# wifi_bluetooth.net
KiCad netlist of a schematic drawn in Altium Designer
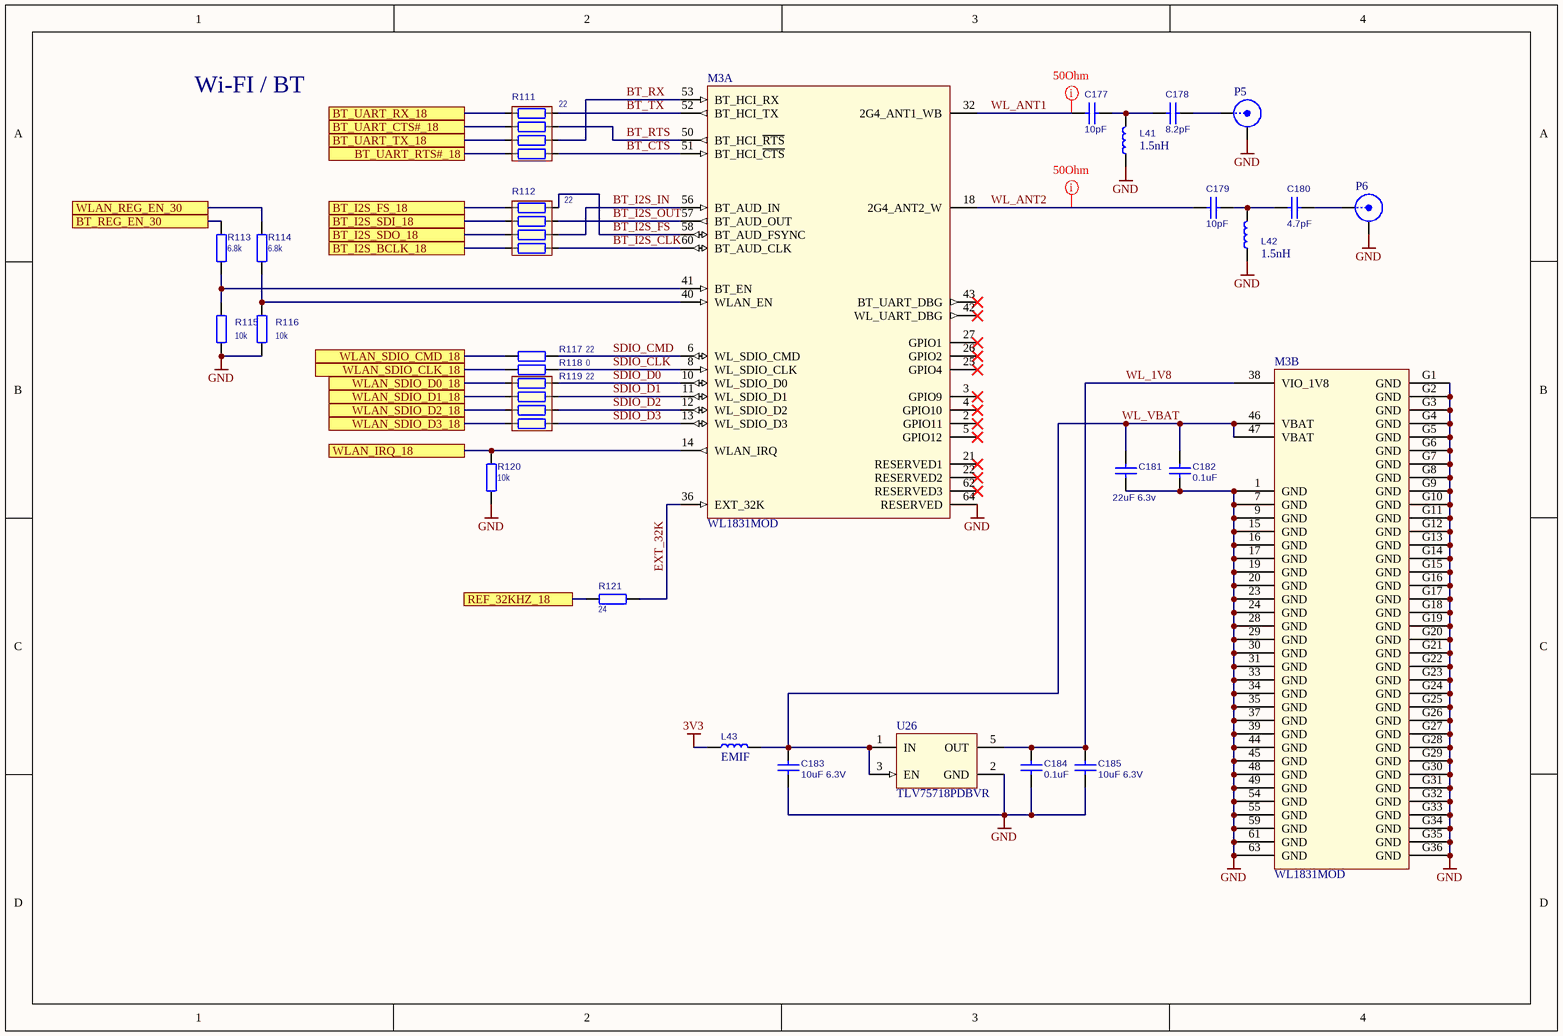
[diagram p0: wifi_bluetooth.SchDoc]

(export (version "E")
  (design (tool "Eeschema 10.0.6"))
  (components
    (comp (ref "C177")
      (value "10pF")
      (footprint "C0603")
      (description "CAP_NPOL")
      (fields (field (name "Comment") "CL10C100JB8NNNC"))
      (libsource (lib "capacitors") (part "CAP_NPOL"))
    )
    (comp (ref "C178")
      (value "8.2pF")
      (footprint "C0603")
      (description "CAP_NPOL")
      (fields (field (name "Comment") "CL10C8R2CB8NNNC"))
      (libsource (lib "capacitors") (part "CAP_NPOL"))
    )
    (comp (ref "C179")
      (value "10pF")
      (footprint "C0603")
      (description "CAP_NPOL")
      (fields (field (name "Comment") "CL10C100JB8NNNC"))
      (libsource (lib "capacitors") (part "CAP_NPOL"))
    )
    (comp (ref "C180")
      (value "4.7pF")
      (footprint "C0603")
      (description "CAP_NPOL")
      (fields (field (name "Comment") "CC0603CRNPO9BN4R7"))
      (libsource (lib "capacitors") (part "CAP_NPOL"))
    )
    (comp (ref "C181")
      (value "22uF 6.3v")
      (footprint "Capacitors:C0805")
      (description "CAP_NPOL")
      (fields (field (name "Comment") "CL21A226MQQNNNE"))
      (libsource (lib "capacitors") (part "CAP_NPOL"))
    )
    (comp (ref "C182")
      (value "0.1uF")
      (footprint "Capacitors:C0603")
      (description "CAP_NPOL")
      (fields (field (name "Comment") "C1608X7R1H104K080AA"))
      (libsource (lib "capacitors") (part "CAP_NPOL"))
    )
    (comp (ref "C183")
      (value "10uF 6.3V")
      (footprint "Capacitors:C0603")
      (description "CAP_NPOL")
      (fields (field (name "Comment") "CC0603MRX5R5BB106"))
      (libsource (lib "capacitors") (part "CAP_NPOL"))
    )
    (comp (ref "C184")
      (value "0.1uF")
      (footprint "Capacitors:C0603")
      (description "CAP_NPOL")
      (fields (field (name "Comment") "C1608X7R1H104K080AA"))
      (libsource (lib "capacitors") (part "CAP_NPOL"))
    )
    (comp (ref "C185")
      (value "10uF 6.3V")
      (footprint "Capacitors:C0603")
      (description "CAP_NPOL")
      (fields (field (name "Comment") "CC0603MRX5R5BB106"))
      (libsource (lib "capacitors") (part "CAP_NPOL"))
    )
    (comp (ref "L41")
      (value "1.5nH")
      (footprint "IND0603")
      (description "IND_WO_IRON")
      (fields (field (name "Comment") "CLH1608T-1N5S-N"))
      (libsource (lib "inductors") (part "IND_WO_IRON"))
    )
    (comp (ref "L42")
      (value "1.5nH")
      (footprint "IND0603")
      (description "IND_WO_IRON")
      (fields (field (name "Comment") "CLH1608T-1N5S-N"))
      (libsource (lib "inductors") (part "IND_WO_IRON"))
    )
    (comp (ref "L43")
      (value "EMIF")
      (footprint "IND0805")
      (description "IND_WO_IRON")
      (fields (field (name "Comment") "BLM21PG221SN1D"))
      (libsource (lib "") (part "IND_WO_IRON_1"))
    )
    (comp (ref "M3")
      (value "WL1831MOD")
      (footprint "E-13.4X13.3-N100_0.75-TOP")
      (libsource (lib "WL18xxMOD") (part "WL18xxMOD"))
    )
    (comp (ref "P5")
      (value "I-PEX")
      (footprint "RF:I-PEX")
      (fields (field (name "PUBLISHER") "Altium Limited"))
      (libsource (lib "Miscellaneous Connectors") (part "BNC"))
    )
    (comp (ref "P6")
      (value "I-PEX")
      (footprint "RF:I-PEX")
      (fields (field (name "PUBLISHER") "Altium Limited"))
      (libsource (lib "Miscellaneous Connectors") (part "BNC"))
    )
    (comp (ref "R111")
      (value "22")
      (footprint "Resistors:R0804X4")
      (description "ARRAY")
      (fields (field (name "Comment") "TC124-JR-0722RL"))
      (libsource (lib "") (part "ARRAY_1"))
    )
    (comp (ref "R112")
      (value "22")
      (footprint "Resistors:R0804X4")
      (description "ARRAY")
      (fields (field (name "Comment") "TC124-JR-0722RL"))
      (libsource (lib "") (part "ARRAY_1"))
    )
    (comp (ref "R113")
      (value "6.8k")
      (footprint "R0603")
      (description "RES")
      (libsource (lib "resistors") (part "RESISTOR"))
    )
    (comp (ref "R114")
      (value "6.8k")
      (footprint "R0603")
      (description "RES")
      (libsource (lib "resistors") (part "RESISTOR"))
    )
    (comp (ref "R115")
      (value "10k")
      (footprint "R0603")
      (description "RES")
      (libsource (lib "resistors") (part "RESISTOR"))
    )
    (comp (ref "R116")
      (value "10k")
      (footprint "R0603")
      (description "RES")
      (libsource (lib "resistors") (part "RESISTOR"))
    )
    (comp (ref "R117")
      (value "22")
      (footprint "R0603")
      (description "RES")
      (libsource (lib "resistors") (part "RESISTOR"))
    )
    (comp (ref "R118")
      (value "0")
      (footprint "Resistors:R0603")
      (description "RES")
      (libsource (lib "resistors") (part "RESISTOR"))
    )
    (comp (ref "R119")
      (value "22")
      (footprint "Resistors:R0804X4")
      (description "ARRAY")
      (fields (field (name "Comment") "TC124-JR-0722RL"))
      (libsource (lib "resistors") (part "ARRAY"))
    )
    (comp (ref "R120")
      (value "10k")
      (footprint "R0603")
      (description "RES")
      (libsource (lib "resistors") (part "RESISTOR"))
    )
    (comp (ref "R121")
      (value "24")
      (footprint "R0603")
      (description "RES")
      (libsource (lib "resistors") (part "RESISTOR"))
    )
    (comp (ref "U26")
      (value "TLV75718PDBVR")
      (footprint "SOT-23-5")
      (description "Capacitor-Free, 300-mA, Low-Dropout Regulator with Foldback Current Limit for Portable Devices")
      (libsource (lib "TLV733P") (part "TLV733P"))
    )
  )
  (nets
    (net (code "1") (name "/BT_CTS") (class "Default")
      (node (ref "M3") (pin "51") (pinfunction "BT_HCI_~{CTS}_51") (pintype "input"))
      (node (ref "R111") (pin "8") (pinfunction "8_8") (pintype "passive"))
    )
    (net (code "2") (name "/BT_I2S_BCLK_18") (class "Default")
      (node (ref "R112") (pin "7") (pinfunction "7_7") (pintype "passive"))
    )
    (net (code "3") (name "/BT_I2S_CLK") (class "Default")
      (node (ref "M3") (pin "60") (pinfunction "BT_AUD_CLK_60") (pintype "bidirectional"))
      (node (ref "R112") (pin "8") (pinfunction "8_8") (pintype "passive"))
    )
    (net (code "4") (name "/BT_I2S_FS") (class "Default")
      (node (ref "M3") (pin "58") (pinfunction "BT_AUD_FSYNC_58") (pintype "bidirectional"))
      (node (ref "R112") (pin "2") (pinfunction "2_2") (pintype "passive"))
    )
    (net (code "5") (name "/BT_I2S_FS_18") (class "Default")
      (node (ref "R112") (pin "1") (pinfunction "1_1") (pintype "passive"))
    )
    (net (code "6") (name "/BT_I2S_IN") (class "Default")
      (node (ref "M3") (pin "56") (pinfunction "BT_AUD_IN_56") (pintype "input"))
      (node (ref "R112") (pin "6") (pinfunction "6_6") (pintype "passive"))
    )
    (net (code "7") (name "/BT_I2S_OUT") (class "Default")
      (node (ref "M3") (pin "57") (pinfunction "BT_AUD_OUT_57") (pintype "output"))
      (node (ref "R112") (pin "4") (pinfunction "4_4") (pintype "passive"))
    )
    (net (code "8") (name "/BT_I2S_SDI_18") (class "Default")
      (node (ref "R112") (pin "3") (pinfunction "3_3") (pintype "passive"))
    )
    (net (code "9") (name "/BT_I2S_SDO_18") (class "Default")
      (node (ref "R112") (pin "5") (pinfunction "5_5") (pintype "passive"))
    )
    (net (code "10") (name "/BT_REG_EN_30") (class "Default")
      (node (ref "R113") (pin "1") (pinfunction "1_1") (pintype "passive"))
    )
    (net (code "11") (name "/BT_RTS") (class "Default")
      (node (ref "M3") (pin "50") (pinfunction "BT_HCI_~{RTS}_50") (pintype "output"))
      (node (ref "R111") (pin "4") (pinfunction "4_4") (pintype "passive"))
    )
    (net (code "12") (name "/BT_RX") (class "Default")
      (node (ref "M3") (pin "53") (pinfunction "BT_HCI_RX_53") (pintype "input"))
      (node (ref "R111") (pin "6") (pinfunction "6_6") (pintype "passive"))
    )
    (net (code "13") (name "/BT_TX") (class "Default")
      (node (ref "M3") (pin "52") (pinfunction "BT_HCI_TX_52") (pintype "output"))
      (node (ref "R111") (pin "2") (pinfunction "2_2") (pintype "passive"))
    )
    (net (code "14") (name "/BT_UART_CTS#_18") (class "Default")
      (node (ref "R111") (pin "3") (pinfunction "3_3") (pintype "passive"))
    )
    (net (code "15") (name "/BT_UART_RTS#_18") (class "Default")
      (node (ref "R111") (pin "7") (pinfunction "7_7") (pintype "passive"))
    )
    (net (code "16") (name "/BT_UART_RX_18") (class "Default")
      (node (ref "R111") (pin "1") (pinfunction "1_1") (pintype "passive"))
    )
    (net (code "17") (name "/BT_UART_TX_18") (class "Default")
      (node (ref "R111") (pin "5") (pinfunction "5_5") (pintype "passive"))
    )
    (net (code "18") (name "/EXT_32K") (class "Default")
      (node (ref "M3") (pin "36") (pinfunction "EXT_32K_36") (pintype "input"))
      (node (ref "R121") (pin "2") (pinfunction "2_2") (pintype "passive"))
    )
    (net (code "19") (name "/REF_32KHZ_18") (class "Default")
      (node (ref "R121") (pin "1") (pinfunction "1_1") (pintype "passive"))
    )
    (net (code "20") (name "/SDIO_CLK") (class "Default")
      (node (ref "M3") (pin "8") (pinfunction "WL_SDIO_CLK_8") (pintype "input"))
      (node (ref "R118") (pin "1") (pinfunction "1_1") (pintype "passive"))
    )
    (net (code "21") (name "/SDIO_CMD") (class "Default")
      (node (ref "M3") (pin "6") (pinfunction "WL_SDIO_CMD_6") (pintype "bidirectional"))
      (node (ref "R117") (pin "1") (pinfunction "1_1") (pintype "passive"))
    )
    (net (code "22") (name "/SDIO_D0") (class "Default")
      (node (ref "M3") (pin "10") (pinfunction "WL_SDIO_D0_10") (pintype "bidirectional"))
      (node (ref "R119") (pin "1") (pinfunction "1_1") (pintype "passive"))
    )
    (net (code "23") (name "/SDIO_D1") (class "Default")
      (node (ref "M3") (pin "11") (pinfunction "WL_SDIO_D1_11") (pintype "bidirectional"))
      (node (ref "R119") (pin "3") (pinfunction "3_3") (pintype "passive"))
    )
    (net (code "24") (name "/SDIO_D2") (class "Default")
      (node (ref "M3") (pin "12") (pinfunction "WL_SDIO_D2_12") (pintype "bidirectional"))
      (node (ref "R119") (pin "5") (pinfunction "5_5") (pintype "passive"))
    )
    (net (code "25") (name "/SDIO_D3") (class "Default")
      (node (ref "M3") (pin "13") (pinfunction "WL_SDIO_D3_13") (pintype "bidirectional"))
      (node (ref "R119") (pin "7") (pinfunction "7_7") (pintype "passive"))
    )
    (net (code "26") (name "/WLAN_IRQ_18") (class "Default")
      (node (ref "M3") (pin "14") (pinfunction "WLAN_IRQ_14") (pintype "output"))
      (node (ref "R120") (pin "2") (pinfunction "2_2") (pintype "passive"))
    )
    (net (code "27") (name "/WLAN_REG_EN_30") (class "Default")
      (node (ref "R114") (pin "1") (pinfunction "1_1") (pintype "passive"))
    )
    (net (code "28") (name "/WLAN_SDIO_CLK_18") (class "Default")
      (node (ref "R118") (pin "2") (pinfunction "2_2") (pintype "passive"))
    )
    (net (code "29") (name "/WLAN_SDIO_CMD_18") (class "Default")
      (node (ref "R117") (pin "2") (pinfunction "2_2") (pintype "passive"))
    )
    (net (code "30") (name "/WLAN_SDIO_D0_18") (class "Default")
      (node (ref "R119") (pin "2") (pinfunction "2_2") (pintype "passive"))
    )
    (net (code "31") (name "/WLAN_SDIO_D1_18") (class "Default")
      (node (ref "R119") (pin "4") (pinfunction "4_4") (pintype "passive"))
    )
    (net (code "32") (name "/WLAN_SDIO_D2_18") (class "Default")
      (node (ref "R119") (pin "6") (pinfunction "6_6") (pintype "passive"))
    )
    (net (code "33") (name "/WLAN_SDIO_D3_18") (class "Default")
      (node (ref "R119") (pin "8") (pinfunction "8_8") (pintype "passive"))
    )
    (net (code "34") (name "/WL_1V8") (class "Default")
      (node (ref "C184") (pin "1") (pinfunction "1_1") (pintype "passive"))
      (node (ref "C185") (pin "1") (pinfunction "1_1") (pintype "passive"))
      (node (ref "M3") (pin "38") (pinfunction "VIO_1V8_38") (pintype "power_in"))
      (node (ref "U26") (pin "5") (pinfunction "OUT_5") (pintype "power_in"))
    )
    (net (code "35") (name "/WL_ANT1") (class "Default")
      (node (ref "C177") (pin "1") (pinfunction "1_1") (pintype "passive"))
      (node (ref "M3") (pin "32") (pinfunction "2G4_ANT1_WB_32") (pintype "passive"))
    )
    (net (code "36") (name "/WL_ANT2") (class "Default")
      (node (ref "C179") (pin "1") (pinfunction "1_1") (pintype "passive"))
      (node (ref "M3") (pin "18") (pinfunction "2G4_ANT2_W_18") (pintype "passive"))
    )
    (net (code "37") (name "/WL_VBAT") (class "Default")
      (node (ref "C181") (pin "2") (pinfunction "2_2") (pintype "passive"))
      (node (ref "C182") (pin "2") (pinfunction "2_2") (pintype "passive"))
      (node (ref "C183") (pin "1") (pinfunction "1_1") (pintype "passive"))
      (node (ref "L43") (pin "1") (pintype "passive"))
      (node (ref "M3") (pin "46") (pinfunction "VBAT_46") (pintype "power_in"))
      (node (ref "M3") (pin "47") (pinfunction "VBAT_47") (pintype "power_in"))
      (node (ref "U26") (pin "1") (pinfunction "IN_1") (pintype "power_in"))
      (node (ref "U26") (pin "3") (pinfunction "EN_3") (pintype "input"))
    )
    (net (code "38") (name "3V3") (class "Default") (node (ref "L43") (pin "2") (pintype "passive")))
    (net (code "39") (name "GND") (class "Default")
      (node (ref "C181") (pin "1") (pinfunction "1_1") (pintype "passive"))
      (node (ref "C182") (pin "1") (pinfunction "1_1") (pintype "passive"))
      (node (ref "C183") (pin "2") (pinfunction "2_2") (pintype "passive"))
      (node (ref "C184") (pin "2") (pinfunction "2_2") (pintype "passive"))
      (node (ref "C185") (pin "2") (pinfunction "2_2") (pintype "passive"))
      (node (ref "L41") (pin "1") (pintype "passive"))
      (node (ref "L42") (pin "1") (pintype "passive"))
      (node (ref "M3") (pin "1") (pinfunction "GND_1") (pintype "power_in"))
      (node (ref "M3") (pin "15") (pinfunction "GND_15") (pintype "power_in"))
      (node (ref "M3") (pin "16") (pinfunction "GND_16") (pintype "power_in"))
      (node (ref "M3") (pin "17") (pinfunction "GND_17") (pintype "power_in"))
      (node (ref "M3") (pin "19") (pinfunction "GND_19") (pintype "power_in"))
      (node (ref "M3") (pin "20") (pinfunction "GND_20") (pintype "power_in"))
      (node (ref "M3") (pin "23") (pinfunction "GND_23") (pintype "power_in"))
      (node (ref "M3") (pin "24") (pinfunction "GND_24") (pintype "power_in"))
      (node (ref "M3") (pin "28") (pinfunction "GND_28") (pintype "power_in"))
      (node (ref "M3") (pin "29") (pinfunction "GND_29") (pintype "power_in"))
      (node (ref "M3") (pin "30") (pinfunction "GND_30") (pintype "power_in"))
      (node (ref "M3") (pin "31") (pinfunction "GND_31") (pintype "power_in"))
      (node (ref "M3") (pin "33") (pinfunction "GND_33") (pintype "power_in"))
      (node (ref "M3") (pin "34") (pinfunction "GND_34") (pintype "power_in"))
      (node (ref "M3") (pin "35") (pinfunction "GND_35") (pintype "power_in"))
      (node (ref "M3") (pin "37") (pinfunction "GND_37") (pintype "power_in"))
      (node (ref "M3") (pin "39") (pinfunction "GND_39") (pintype "power_in"))
      (node (ref "M3") (pin "44") (pinfunction "GND_44") (pintype "power_in"))
      (node (ref "M3") (pin "45") (pinfunction "GND_45") (pintype "power_in"))
      (node (ref "M3") (pin "48") (pinfunction "GND_48") (pintype "power_in"))
      (node (ref "M3") (pin "49") (pinfunction "GND_49") (pintype "power_in"))
      (node (ref "M3") (pin "54") (pinfunction "GND_54") (pintype "power_in"))
      (node (ref "M3") (pin "55") (pinfunction "GND_55") (pintype "power_in"))
      (node (ref "M3") (pin "59") (pinfunction "GND_59") (pintype "power_in"))
      (node (ref "M3") (pin "61") (pinfunction "GND_61") (pintype "power_in"))
      (node (ref "M3") (pin "63") (pinfunction "GND_63") (pintype "power_in"))
      (node (ref "M3") (pin "64") (pinfunction "RESERVED_64") (pintype "passive"))
      (node (ref "M3") (pin "7") (pinfunction "GND_7") (pintype "power_in"))
      (node (ref "M3") (pin "9") (pinfunction "GND_9") (pintype "power_in"))
      (node (ref "M3") (pin "G1") (pinfunction "GND_G1") (pintype "power_in"))
      (node (ref "M3") (pin "G10") (pinfunction "GND_G10") (pintype "power_in"))
      (node (ref "M3") (pin "G11") (pinfunction "GND_G11") (pintype "power_in"))
      (node (ref "M3") (pin "G12") (pinfunction "GND_G12") (pintype "power_in"))
      (node (ref "M3") (pin "G13") (pinfunction "GND_G13") (pintype "power_in"))
      (node (ref "M3") (pin "G14") (pinfunction "GND_G14") (pintype "power_in"))
      (node (ref "M3") (pin "G15") (pinfunction "GND_G15") (pintype "power_in"))
      (node (ref "M3") (pin "G16") (pinfunction "GND_G16") (pintype "power_in"))
      (node (ref "M3") (pin "G17") (pinfunction "GND_G17") (pintype "power_in"))
      (node (ref "M3") (pin "G18") (pinfunction "GND_G18") (pintype "power_in"))
      (node (ref "M3") (pin "G19") (pinfunction "GND_G19") (pintype "power_in"))
      (node (ref "M3") (pin "G2") (pinfunction "GND_G2") (pintype "power_in"))
      (node (ref "M3") (pin "G20") (pinfunction "GND_G20") (pintype "power_in"))
      (node (ref "M3") (pin "G21") (pinfunction "GND_G21") (pintype "power_in"))
      (node (ref "M3") (pin "G22") (pinfunction "GND_G22") (pintype "power_in"))
      (node (ref "M3") (pin "G23") (pinfunction "GND_G23") (pintype "power_in"))
      (node (ref "M3") (pin "G24") (pinfunction "GND_G24") (pintype "power_in"))
      (node (ref "M3") (pin "G25") (pinfunction "GND_G25") (pintype "power_in"))
      (node (ref "M3") (pin "G26") (pinfunction "GND_G26") (pintype "power_in"))
      (node (ref "M3") (pin "G27") (pinfunction "GND_G27") (pintype "power_in"))
      (node (ref "M3") (pin "G28") (pinfunction "GND_G28") (pintype "power_in"))
      (node (ref "M3") (pin "G29") (pinfunction "GND_G29") (pintype "power_in"))
      (node (ref "M3") (pin "G3") (pinfunction "GND_G3") (pintype "power_in"))
      (node (ref "M3") (pin "G30") (pinfunction "GND_G30") (pintype "power_in"))
      (node (ref "M3") (pin "G31") (pinfunction "GND_G31") (pintype "power_in"))
      (node (ref "M3") (pin "G32") (pinfunction "GND_G32") (pintype "power_in"))
      (node (ref "M3") (pin "G33") (pinfunction "GND_G33") (pintype "power_in"))
      (node (ref "M3") (pin "G34") (pinfunction "GND_G34") (pintype "power_in"))
      (node (ref "M3") (pin "G35") (pinfunction "GND_G35") (pintype "power_in"))
      (node (ref "M3") (pin "G36") (pinfunction "GND_G36") (pintype "power_in"))
      (node (ref "M3") (pin "G4") (pinfunction "GND_G4") (pintype "power_in"))
      (node (ref "M3") (pin "G5") (pinfunction "GND_G5") (pintype "power_in"))
      (node (ref "M3") (pin "G6") (pinfunction "GND_G6") (pintype "power_in"))
      (node (ref "M3") (pin "G7") (pinfunction "GND_G7") (pintype "power_in"))
      (node (ref "M3") (pin "G8") (pinfunction "GND_G8") (pintype "power_in"))
      (node (ref "M3") (pin "G9") (pinfunction "GND_G9") (pintype "power_in"))
      (node (ref "P5") (pin "2") (pinfunction "Y_2") (pintype "passive"))
      (node (ref "P6") (pin "2") (pinfunction "Y_2") (pintype "passive"))
      (node (ref "R115") (pin "2") (pinfunction "2_2") (pintype "passive"))
      (node (ref "R116") (pin "1") (pinfunction "1_1") (pintype "passive"))
      (node (ref "R120") (pin "1") (pinfunction "1_1") (pintype "passive"))
      (node (ref "U26") (pin "2") (pinfunction "GND_2") (pintype "power_in"))
    )
    (net (code "40") (name "Net-(C177-Pad2)") (class "Default")
      (node (ref "C177") (pin "2") (pinfunction "2_2") (pintype "passive"))
      (node (ref "C178") (pin "1") (pinfunction "1_1") (pintype "passive"))
      (node (ref "L41") (pin "2") (pintype "passive"))
    )
    (net (code "41") (name "Net-(C179-Pad2)") (class "Default")
      (node (ref "C179") (pin "2") (pinfunction "2_2") (pintype "passive"))
      (node (ref "C180") (pin "1") (pinfunction "1_1") (pintype "passive"))
      (node (ref "L42") (pin "2") (pintype "passive"))
    )
    (net (code "42") (name "Net-(M3A-BT_EN)") (class "Default")
      (node (ref "M3") (pin "41") (pinfunction "BT_EN_41") (pintype "input"))
      (node (ref "R113") (pin "2") (pinfunction "2_2") (pintype "passive"))
      (node (ref "R115") (pin "1") (pinfunction "1_1") (pintype "passive"))
    )
    (net (code "43") (name "Net-(M3A-WLAN_EN)") (class "Default")
      (node (ref "M3") (pin "40") (pinfunction "WLAN_EN_40") (pintype "input"))
      (node (ref "R114") (pin "2") (pinfunction "2_2") (pintype "passive"))
      (node (ref "R116") (pin "2") (pinfunction "2_2") (pintype "passive"))
    )
    (net (code "44") (name "Net-(P5-X)") (class "Default")
      (node (ref "C178") (pin "2") (pinfunction "2_2") (pintype "passive"))
      (node (ref "P5") (pin "1") (pinfunction "X_1") (pintype "passive"))
    )
    (net (code "45") (name "Net-(P6-X)") (class "Default")
      (node (ref "C180") (pin "2") (pinfunction "2_2") (pintype "passive"))
      (node (ref "P6") (pin "1") (pinfunction "X_1") (pintype "passive"))
    )
    (net (code "46") (name "unconnected-(M3A-BT_UART_DBG-Pad43)") (class "Default")
      (node (ref "M3") (pin "43") (pinfunction "BT_UART_DBG_43") (pintype "output+no_connect"))
    )
    (net (code "47") (name "unconnected-(M3A-GPIO1-Pad27)") (class "Default")
      (node (ref "M3") (pin "27") (pinfunction "GPIO1_27") (pintype "passive+no_connect"))
    )
    (net (code "48") (name "unconnected-(M3A-GPIO2-Pad26)") (class "Default")
      (node (ref "M3") (pin "26") (pinfunction "GPIO2_26") (pintype "passive+no_connect"))
    )
    (net (code "49") (name "unconnected-(M3A-GPIO4-Pad25)") (class "Default")
      (node (ref "M3") (pin "25") (pinfunction "GPIO4_25") (pintype "passive+no_connect"))
    )
    (net (code "50") (name "unconnected-(M3A-GPIO9-Pad3)") (class "Default")
      (node (ref "M3") (pin "3") (pinfunction "GPIO9_3") (pintype "passive+no_connect"))
    )
    (net (code "51") (name "unconnected-(M3A-GPIO10-Pad4)") (class "Default")
      (node (ref "M3") (pin "4") (pinfunction "GPIO10_4") (pintype "passive+no_connect"))
    )
    (net (code "52") (name "unconnected-(M3A-GPIO11-Pad2)") (class "Default")
      (node (ref "M3") (pin "2") (pinfunction "GPIO11_2") (pintype "passive+no_connect"))
    )
    (net (code "53") (name "unconnected-(M3A-GPIO12-Pad5)") (class "Default")
      (node (ref "M3") (pin "5") (pinfunction "GPIO12_5") (pintype "passive+no_connect"))
    )
    (net (code "54") (name "unconnected-(M3A-RESERVED1-Pad21)") (class "Default")
      (node (ref "M3") (pin "21") (pinfunction "RESERVED1_21") (pintype "passive+no_connect"))
    )
    (net (code "55") (name "unconnected-(M3A-RESERVED2-Pad22)") (class "Default")
      (node (ref "M3") (pin "22") (pinfunction "RESERVED2_22") (pintype "passive+no_connect"))
    )
    (net (code "56") (name "unconnected-(M3A-RESERVED3-Pad62)") (class "Default")
      (node (ref "M3") (pin "62") (pinfunction "RESERVED3_62") (pintype "passive+no_connect"))
    )
    (net (code "57") (name "unconnected-(M3A-WL_UART_DBG-Pad42)") (class "Default")
      (node (ref "M3") (pin "42") (pinfunction "WL_UART_DBG_42") (pintype "output+no_connect"))
    )
  )
)
